# picr22-team-GibiBot-mainboard1.net
KiCad netlist of a schematic drawn in Altium Designer
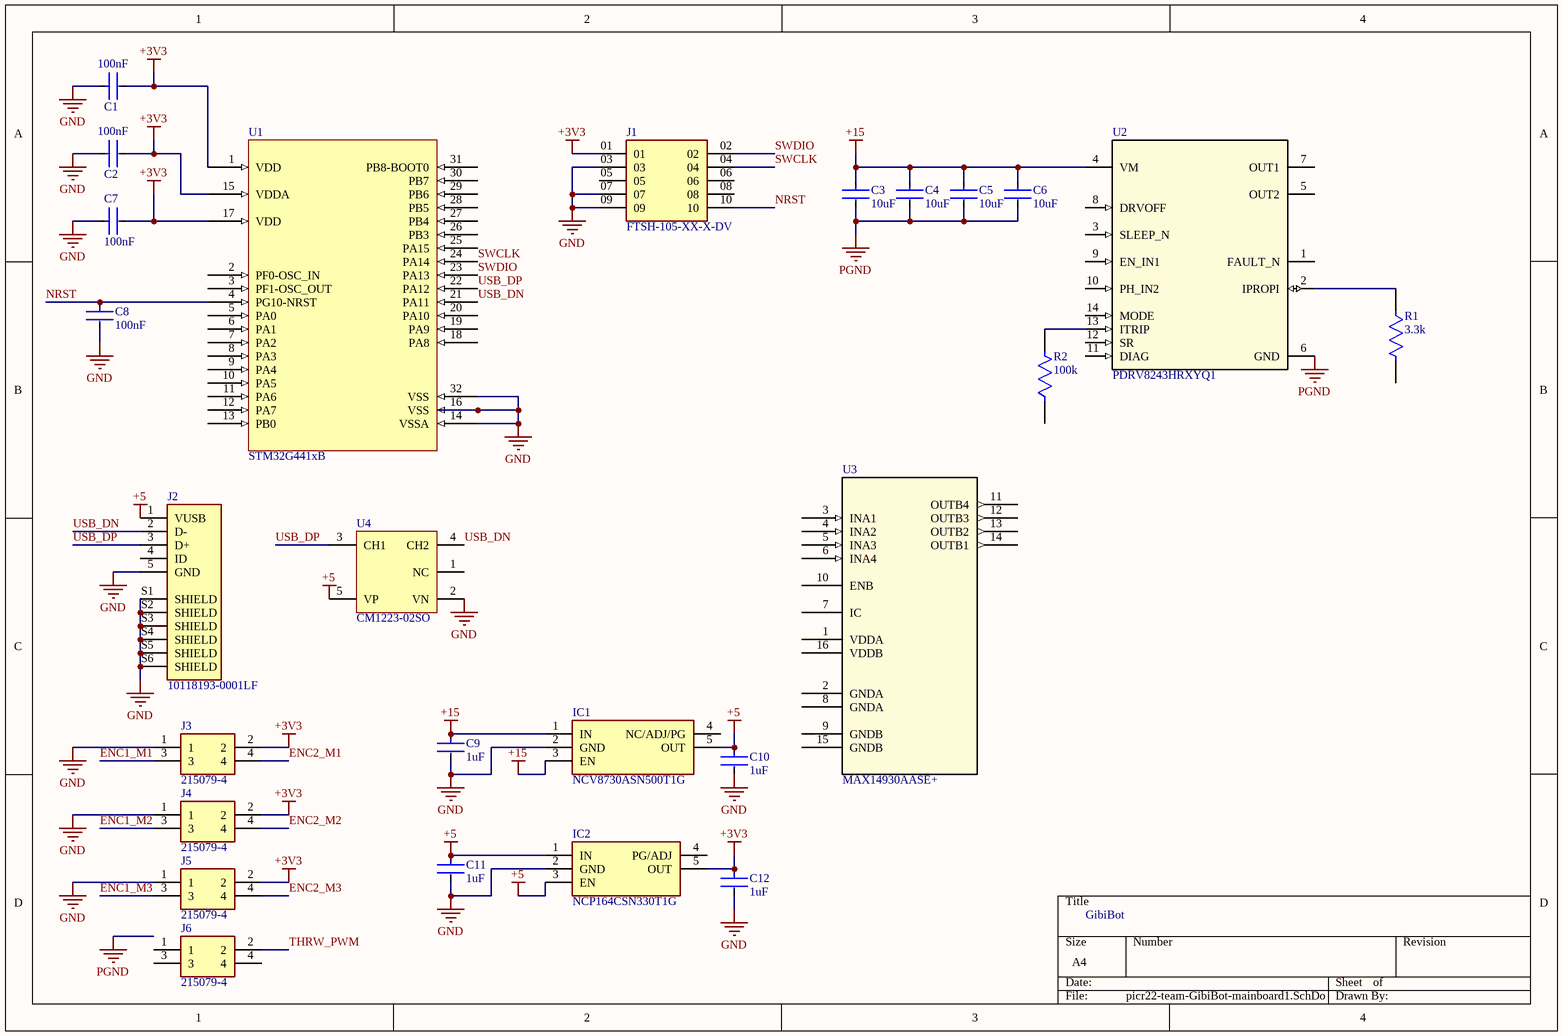
[diagram p0: picr22-team-GibiBot-mainboard1.SchDoc]

(export (version "E")
  (design (tool "Eeschema 10.0.6"))
  (components
    (comp (ref "C1")
      (value "CGA3E2X7R1H104K080AA")
      (footprint "FP-CGA3E-0_3-0_1-IPC_A")
      (description "Cap Ceramic 100nF 50V X7R 10% Pad SMD 0603 +125°C Automotive T/R")
      (fields
        (field (name "TOLERANCE") "10%")
        (field (name "CAPACITANCE") "100nF")
        (field (name "VOLTAGE") "50V")
      )
      (libsource (lib "Altium Content Vault") (part "b4654b650e69147ec39a6b967a45e02"))
    )
    (comp (ref "C2")
      (value "CGA3E2X7R1H104K080AA")
      (footprint "FP-CGA3E-0_3-0_1-IPC_A")
      (description "Cap Ceramic 100nF 50V X7R 10% Pad SMD 0603 +125°C Automotive T/R")
      (fields
        (field (name "TOLERANCE") "10%")
        (field (name "CAPACITANCE") "100nF")
        (field (name "VOLTAGE") "50V")
      )
      (libsource (lib "Altium Content Vault") (part "b4654b650e69147ec39a6b967a45e02"))
    )
    (comp (ref "C3")
      (value "CGA3E2X7R1H104K080AA")
      (footprint "FP-CGA3E-0_3-0_1-IPC_A")
      (description "Cap Ceramic 100nF 50V X7R 10% Pad SMD 0603 +125°C Automotive T/R")
      (fields
        (field (name "TOLERANCE") "10%")
        (field (name "CAPACITANCE") "10uF")
        (field (name "VOLTAGE") "50V")
      )
      (libsource (lib "Altium Content Vault") (part "b4654b650e69147ec39a6b967a45e02"))
    )
    (comp (ref "C4")
      (value "CGA3E2X7R1H104K080AA")
      (footprint "FP-CGA3E-0_3-0_1-IPC_A")
      (description "Cap Ceramic 100nF 50V X7R 10% Pad SMD 0603 +125°C Automotive T/R")
      (fields
        (field (name "TOLERANCE") "10%")
        (field (name "CAPACITANCE") "10uF")
        (field (name "VOLTAGE") "50V")
      )
      (libsource (lib "Altium Content Vault") (part "b4654b650e69147ec39a6b967a45e02"))
    )
    (comp (ref "C5")
      (value "CGA3E2X7R1H104K080AA")
      (footprint "FP-CGA3E-0_3-0_1-IPC_A")
      (description "Cap Ceramic 100nF 50V X7R 10% Pad SMD 0603 +125°C Automotive T/R")
      (fields
        (field (name "TOLERANCE") "10%")
        (field (name "CAPACITANCE") "10uF")
        (field (name "VOLTAGE") "50V")
      )
      (libsource (lib "Altium Content Vault") (part "b4654b650e69147ec39a6b967a45e02"))
    )
    (comp (ref "C6")
      (value "CGA3E2X7R1H104K080AA")
      (footprint "FP-CGA3E-0_3-0_1-IPC_A")
      (description "Cap Ceramic 100nF 50V X7R 10% Pad SMD 0603 +125°C Automotive T/R")
      (fields
        (field (name "TOLERANCE") "10%")
        (field (name "CAPACITANCE") "10uF")
        (field (name "VOLTAGE") "50V")
      )
      (libsource (lib "Altium Content Vault") (part "b4654b650e69147ec39a6b967a45e02"))
    )
    (comp (ref "C7")
      (value "CGA3E2X7R1H104K080AA")
      (footprint "FP-CGA3E-0_3-0_1-IPC_A")
      (description "Cap Ceramic 100nF 50V X7R 10% Pad SMD 0603 +125°C Automotive T/R")
      (fields
        (field (name "TOLERANCE") "10%")
        (field (name "CAPACITANCE") "100nF")
        (field (name "VOLTAGE") "50V")
      )
      (libsource (lib "Altium Content Vault") (part "b4654b650e69147ec39a6b967a45e02"))
    )
    (comp (ref "C8")
      (value "CGA3E2X7R1H104K080AA")
      (footprint "FP-CGA3E-0_3-0_1-IPC_A")
      (description "Cap Ceramic 100nF 50V X7R 10% Pad SMD 0603 +125°C Automotive T/R")
      (fields
        (field (name "TOLERANCE") "10%")
        (field (name "CAPACITANCE") "100nF")
        (field (name "VOLTAGE") "50V")
      )
      (libsource (lib "Altium Content Vault") (part "b4654b650e69147ec39a6b967a45e02"))
    )
    (comp (ref "C9")
      (value "CGA3E2X7R1H104K080AA")
      (footprint "FP-CGA3E-0_3-0_1-IPC_A")
      (description "Cap Ceramic 100nF 50V X7R 10% Pad SMD 0603 +125°C Automotive T/R")
      (fields
        (field (name "TOLERANCE") "10%")
        (field (name "CAPACITANCE") "1uF")
        (field (name "VOLTAGE") "50V")
      )
      (libsource (lib "Altium Content Vault") (part "b4654b650e69147ec39a6b967a45e02"))
    )
    (comp (ref "C10")
      (value "CGA3E2X7R1H104K080AA")
      (footprint "FP-CGA3E-0_3-0_1-IPC_A")
      (description "Cap Ceramic 100nF 50V X7R 10% Pad SMD 0603 +125°C Automotive T/R")
      (fields
        (field (name "TOLERANCE") "10%")
        (field (name "CAPACITANCE") "1uF")
        (field (name "VOLTAGE") "50V")
      )
      (libsource (lib "Altium Content Vault") (part "b4654b650e69147ec39a6b967a45e02"))
    )
    (comp (ref "C11")
      (value "CGA3E2X7R1H104K080AA")
      (footprint "FP-CGA3E-0_3-0_1-IPC_A")
      (description "Cap Ceramic 100nF 50V X7R 10% Pad SMD 0603 +125°C Automotive T/R")
      (fields
        (field (name "TOLERANCE") "10%")
        (field (name "CAPACITANCE") "1uF")
        (field (name "VOLTAGE") "50V")
      )
      (libsource (lib "Altium Content Vault") (part "b4654b650e69147ec39a6b967a45e02"))
    )
    (comp (ref "C12")
      (value "CGA3E2X7R1H104K080AA")
      (footprint "FP-CGA3E-0_3-0_1-IPC_A")
      (description "Cap Ceramic 100nF 50V X7R 10% Pad SMD 0603 +125°C Automotive T/R")
      (fields
        (field (name "TOLERANCE") "10%")
        (field (name "CAPACITANCE") "1uF")
        (field (name "VOLTAGE") "50V")
      )
      (libsource (lib "Altium Content Vault") (part "b4654b650e69147ec39a6b967a45e02"))
    )
    (comp (ref "IC1")
      (value "NCV8730ASN500T1G")
      (footprint "SamacSys:SOT95P275X110-5N")
      (description "Integrated Circuit")
      (fields (field (name "MOUSER PART NUMBER") "863-NCV8730ASN500T1G"))
      (libsource (lib "*") (part "NCV8730ASN500T1G"))
    )
    (comp (ref "IC2")
      (value "NCP164CSN330T1G")
      (footprint "SamacSys:SOT95P275X110-5N")
      (description "Integrated Circuit")
      (fields (field (name "MOUSER PART NUMBER") "863-NCP164CSN330T1G"))
      (libsource (lib "*") (part "NCP164CSN330T1G"))
    )
    (comp (ref "J1")
      (value "FTSH-105-XX-X-DV")
      (footprint "SAMTEC_FTSH-105-XX-X-DV")
      (description "Connector Header Surface Mount 10 position 0.050\" (1.27mm)")
      (libsource (lib "FTSH-105-XX-X-DV") (part "FTSH-105-XX-X-DV"))
    )
    (comp (ref "J2")
      (value "10118193-0001LF")
      (footprint "FCI_10118193-0001LF")
      (description "USB - micro B USB 2.0 Receptacle Connector 5 Position Surface Mount, Right Angle; Through Hole")
      (fields (field (name "MF") "Amphenol ICC"))
      (libsource (lib "10118193-0001LF") (part "10118193-0001LF"))
    )
    (comp (ref "J3")
      (value "215079-4")
      (footprint "TE_215079-4")
      (description "4 Position Receptacle Connector Through Hole")
      (fields (field (name "MF") "TE Connectivity"))
      (libsource (lib "215079-4") (part "215079-4"))
    )
    (comp (ref "J4")
      (value "215079-4")
      (footprint "TE_215079-4")
      (description "4 Position Receptacle Connector Through Hole")
      (fields (field (name "MF") "TE Connectivity"))
      (libsource (lib "215079-4") (part "215079-4"))
    )
    (comp (ref "J5")
      (value "215079-4")
      (footprint "TE_215079-4")
      (description "4 Position Receptacle Connector Through Hole")
      (fields (field (name "MF") "TE Connectivity"))
      (libsource (lib "215079-4") (part "215079-4"))
    )
    (comp (ref "J6")
      (value "215079-4")
      (footprint "TE_215079-4")
      (description "4 Position Receptacle Connector Through Hole")
      (fields (field (name "MF") "TE Connectivity"))
      (libsource (lib "215079-4") (part "215079-4"))
    )
    (comp (ref "R1")
      (value "CRCW040232K4FKED")
      (footprint "FP-CRCW0402-e3-MFG")
      (description "RES Thick Film, 32.4kΩ, 1%, 0.063W, 100ppm/°C, 0402")
      (fields (field (name "RESISTANCE") "3.3k") (field (name "TOLERANCE") "1%"))
      (libsource (lib "Altium Content Vault") (part "1029c3af85768c4190bb7ad29bc67b5"))
    )
    (comp (ref "R2")
      (value "CRCW040232K4FKED")
      (footprint "FP-CRCW0402-e3-MFG")
      (description "RES Thick Film, 32.4kΩ, 1%, 0.063W, 100ppm/°C, 0402")
      (fields (field (name "RESISTANCE") "100k") (field (name "TOLERANCE") "1%"))
      (libsource (lib "Altium Content Vault") (part "1029c3af85768c4190bb7ad29bc67b5"))
    )
    (comp (ref "U1")
      (value "STM32G441xB")
      (footprint "TQFP80P900X900X160-32N")
      (libsource (lib "picr22-team-GibiBot-mainboard") (part "STM32G441xB"))
    )
    (comp (ref "U2")
      (value "PDRV8243HRXYQ1")
      (footprint "RXY0014A-MFG")
      (description "No Description Available")
      (fields (field (name "COPYRIGHT") "Copyright (C) 2022 Ultra Librarian. All rights reserved."))
      (libsource (lib "PDRV8243HRXYQ1") (part "PDRV8243HRXYQ1"))
    )
    (comp (ref "U3")
      (value "MAX14930AASE+")
      (footprint "21-0041_S16+1_MXM")
      (description "No Description Available")
      (fields (field (name "COPYRIGHT") "Copyright (C) 2022 Ultra Librarian. All rights reserved."))
      (libsource (lib "MAX14930AASE&plus_") (part "MAX14930AASE+"))
    )
    (comp (ref "U4")
      (value "CM1223-02SO")
      (footprint "ONSC-SOT23-5-527AH-01_L")
      (fields (field (name "MANUFACTURER") "On Semiconductor"))
      (libsource (lib "Altium Content Vault") (part "ONSC-CM1223-SOT-23-5-527AH-01"))
    )
  )
  (nets
    (net (code "1") (name "+3V3") (class "Default")
      (node (ref "C1") (pin "2") (pinfunction "2_2") (pintype "passive"))
      (node (ref "C12") (pin "1") (pinfunction "1_1") (pintype "passive"))
      (node (ref "C2") (pin "2") (pinfunction "2_2") (pintype "passive"))
      (node (ref "C7") (pin "2") (pinfunction "2_2") (pintype "passive"))
      (node (ref "IC2") (pin "5") (pinfunction "OUT_5") (pintype "passive"))
      (node (ref "J1") (pin "01") (pinfunction "01_01") (pintype "passive"))
      (node (ref "J3") (pin "2") (pinfunction "2_2") (pintype "passive"))
      (node (ref "J4") (pin "2") (pinfunction "2_2") (pintype "passive"))
      (node (ref "J5") (pin "2") (pinfunction "2_2") (pintype "passive"))
      (node (ref "U1") (pin "1") (pinfunction "VDD_1") (pintype "input"))
      (node (ref "U1") (pin "15") (pinfunction "VDDA_15") (pintype "input"))
      (node (ref "U1") (pin "17") (pinfunction "VDD_17") (pintype "input"))
    )
    (net (code "2") (name "+5") (class "Default")
      (node (ref "C10") (pin "1") (pinfunction "1_1") (pintype "passive"))
      (node (ref "C11") (pin "1") (pinfunction "1_1") (pintype "passive"))
      (node (ref "IC1") (pin "5") (pinfunction "OUT_5") (pintype "passive"))
      (node (ref "IC2") (pin "1") (pinfunction "IN_1") (pintype "passive"))
      (node (ref "IC2") (pin "3") (pinfunction "EN_3") (pintype "passive"))
      (node (ref "J2") (pin "1") (pinfunction "VUSB_1") (pintype "passive"))
      (node (ref "U4") (pin "5") (pinfunction "VP_5") (pintype "power_in"))
    )
    (net (code "3") (name "+15") (class "Default")
      (node (ref "C3") (pin "1") (pinfunction "1_1") (pintype "passive"))
      (node (ref "C4") (pin "1") (pinfunction "1_1") (pintype "passive"))
      (node (ref "C5") (pin "1") (pinfunction "1_1") (pintype "passive"))
      (node (ref "C6") (pin "1") (pinfunction "1_1") (pintype "passive"))
      (node (ref "C9") (pin "1") (pinfunction "1_1") (pintype "passive"))
      (node (ref "IC1") (pin "1") (pinfunction "IN_1") (pintype "passive"))
      (node (ref "IC1") (pin "3") (pinfunction "EN_3") (pintype "passive"))
      (node (ref "U2") (pin "4") (pinfunction "VM_4") (pintype "power_in"))
    )
    (net (code "4") (name "/ENC1_M1") (class "Default")
      (node (ref "J3") (pin "3") (pinfunction "3_3") (pintype "passive"))
    )
    (net (code "5") (name "/ENC1_M2") (class "Default")
      (node (ref "J4") (pin "3") (pinfunction "3_3") (pintype "passive"))
    )
    (net (code "6") (name "/ENC1_M3") (class "Default")
      (node (ref "J5") (pin "3") (pinfunction "3_3") (pintype "passive"))
    )
    (net (code "7") (name "/ENC2_M1") (class "Default")
      (node (ref "J3") (pin "4") (pinfunction "4_4") (pintype "passive"))
    )
    (net (code "8") (name "/ENC2_M2") (class "Default")
      (node (ref "J4") (pin "4") (pinfunction "4_4") (pintype "passive"))
    )
    (net (code "9") (name "/ENC2_M3") (class "Default")
      (node (ref "J5") (pin "4") (pinfunction "4_4") (pintype "passive"))
    )
    (net (code "10") (name "/NRST") (class "Default")
      (node (ref "C8") (pin "1") (pinfunction "1_1") (pintype "passive"))
      (node (ref "J1") (pin "10") (pinfunction "10_10") (pintype "passive"))
      (node (ref "U1") (pin "4") (pinfunction "PG10-NRST_4") (pintype "input"))
    )
    (net (code "11") (name "/SWCLK") (class "Default")
      (node (ref "J1") (pin "04") (pinfunction "04_04") (pintype "passive"))
      (node (ref "U1") (pin "24") (pinfunction "PA14_24") (pintype "input"))
    )
    (net (code "12") (name "/SWDIO") (class "Default")
      (node (ref "J1") (pin "02") (pinfunction "02_02") (pintype "passive"))
      (node (ref "U1") (pin "23") (pinfunction "PA13_23") (pintype "input"))
    )
    (net (code "13") (name "/THRW_PWM") (class "Default")
      (node (ref "J6") (pin "2") (pinfunction "2_2") (pintype "passive"))
    )
    (net (code "14") (name "/USB_DN") (class "Default")
      (node (ref "J2") (pin "2") (pinfunction "D-_2") (pintype "passive"))
      (node (ref "U1") (pin "21") (pinfunction "PA11_21") (pintype "input"))
      (node (ref "U4") (pin "4") (pinfunction "CH2_4") (pintype "passive"))
    )
    (net (code "15") (name "/USB_DP") (class "Default")
      (node (ref "J2") (pin "3") (pinfunction "D+_3") (pintype "passive"))
      (node (ref "U1") (pin "22") (pinfunction "PA12_22") (pintype "input"))
      (node (ref "U4") (pin "3") (pinfunction "CH1_3") (pintype "passive"))
    )
    (net (code "16") (name "GND") (class "Default")
      (node (ref "C1") (pin "1") (pinfunction "1_1") (pintype "passive"))
      (node (ref "C10") (pin "2") (pinfunction "2_2") (pintype "passive"))
      (node (ref "C11") (pin "2") (pinfunction "2_2") (pintype "passive"))
      (node (ref "C12") (pin "2") (pinfunction "2_2") (pintype "passive"))
      (node (ref "C2") (pin "1") (pinfunction "1_1") (pintype "passive"))
      (node (ref "C7") (pin "1") (pinfunction "1_1") (pintype "passive"))
      (node (ref "C8") (pin "2") (pinfunction "2_2") (pintype "passive"))
      (node (ref "C9") (pin "2") (pinfunction "2_2") (pintype "passive"))
      (node (ref "IC1") (pin "2") (pinfunction "GND_2") (pintype "passive"))
      (node (ref "IC2") (pin "2") (pinfunction "GND_2") (pintype "passive"))
      (node (ref "J1") (pin "03") (pinfunction "03_03") (pintype "passive"))
      (node (ref "J1") (pin "07") (pinfunction "07_07") (pintype "passive"))
      (node (ref "J1") (pin "09") (pinfunction "09_09") (pintype "passive"))
      (node (ref "J2") (pin "5") (pinfunction "GND_5") (pintype "passive"))
      (node (ref "J2") (pin "S1") (pinfunction "SHIELD_S1") (pintype "passive"))
      (node (ref "J2") (pin "S2") (pinfunction "SHIELD_S2") (pintype "passive"))
      (node (ref "J2") (pin "S3") (pinfunction "SHIELD_S3") (pintype "passive"))
      (node (ref "J2") (pin "S4") (pinfunction "SHIELD_S4") (pintype "passive"))
      (node (ref "J2") (pin "S5") (pinfunction "SHIELD_S5") (pintype "passive"))
      (node (ref "J2") (pin "S6") (pinfunction "SHIELD_S6") (pintype "passive"))
      (node (ref "J3") (pin "1") (pinfunction "1_1") (pintype "passive"))
      (node (ref "J4") (pin "1") (pinfunction "1_1") (pintype "passive"))
      (node (ref "J5") (pin "1") (pinfunction "1_1") (pintype "passive"))
      (node (ref "U1") (pin "14") (pinfunction "VSSA_14") (pintype "input"))
      (node (ref "U1") (pin "16") (pinfunction "VSS_16") (pintype "input"))
      (node (ref "U1") (pin "32") (pinfunction "VSS_32") (pintype "input"))
      (node (ref "U4") (pin "2") (pinfunction "VN_2") (pintype "power_in"))
    )
    (net (code "17") (name "Net-(U2-IPROPI)") (class "Default")
      (node (ref "R1") (pin "1") (pinfunction "1_1") (pintype "passive"))
      (node (ref "U2") (pin "2") (pinfunction "IPROPI_2") (pintype "bidirectional"))
    )
    (net (code "18") (name "Net-(U2-ITRIP)") (class "Default")
      (node (ref "R2") (pin "2") (pinfunction "2_2") (pintype "passive"))
      (node (ref "U2") (pin "13") (pinfunction "ITRIP_13") (pintype "input"))
    )
    (net (code "19") (name "PGND") (class "Default")
      (node (ref "C3") (pin "2") (pinfunction "2_2") (pintype "passive"))
      (node (ref "C4") (pin "2") (pinfunction "2_2") (pintype "passive"))
      (node (ref "C5") (pin "2") (pinfunction "2_2") (pintype "passive"))
      (node (ref "C6") (pin "2") (pinfunction "2_2") (pintype "passive"))
      (node (ref "U2") (pin "6") (pinfunction "GND_6") (pintype "power_in"))
    )
    (net (code "20") (name "unconnected-(IC1-NC{slash}ADJ{slash}PG-Pad4)") (class "Default")
      (node (ref "IC1") (pin "4") (pinfunction "NC/ADJ/PG_4") (pintype "passive"))
    )
    (net (code "21") (name "unconnected-(IC2-PG{slash}ADJ-Pad4)") (class "Default")
      (node (ref "IC2") (pin "4") (pinfunction "PG/ADJ_4") (pintype "passive"))
    )
    (net (code "22") (name "unconnected-(J1-Pad05)") (class "Default")
      (node (ref "J1") (pin "05") (pinfunction "05_05") (pintype "passive"))
    )
    (net (code "23") (name "unconnected-(J1-Pad06)") (class "Default")
      (node (ref "J1") (pin "06") (pinfunction "06_06") (pintype "passive"))
    )
    (net (code "24") (name "unconnected-(J1-Pad08)") (class "Default")
      (node (ref "J1") (pin "08") (pinfunction "08_08") (pintype "passive"))
    )
    (net (code "25") (name "unconnected-(J2-ID-Pad4)") (class "Default")
      (node (ref "J2") (pin "4") (pinfunction "ID_4") (pintype "passive"))
    )
    (net (code "26") (name "unconnected-(J6-Pad1)") (class "Default")
      (node (ref "J6") (pin "1") (pinfunction "1_1") (pintype "passive"))
    )
    (net (code "27") (name "unconnected-(J6-Pad3)") (class "Default")
      (node (ref "J6") (pin "3") (pinfunction "3_3") (pintype "passive"))
    )
    (net (code "28") (name "unconnected-(J6-Pad4)") (class "Default")
      (node (ref "J6") (pin "4") (pinfunction "4_4") (pintype "passive"))
    )
    (net (code "29") (name "unconnected-(R1-Pad2)") (class "Default")
      (node (ref "R1") (pin "2") (pinfunction "2_2") (pintype "passive"))
    )
    (net (code "30") (name "unconnected-(R2-Pad1)") (class "Default")
      (node (ref "R2") (pin "1") (pinfunction "1_1") (pintype "passive"))
    )
    (net (code "31") (name "unconnected-(U1-PA0-Pad5)") (class "Default")
      (node (ref "U1") (pin "5") (pinfunction "PA0_5") (pintype "input"))
    )
    (net (code "32") (name "unconnected-(U1-PA1-Pad6)") (class "Default")
      (node (ref "U1") (pin "6") (pinfunction "PA1_6") (pintype "input"))
    )
    (net (code "33") (name "unconnected-(U1-PA2-Pad7)") (class "Default")
      (node (ref "U1") (pin "7") (pinfunction "PA2_7") (pintype "input"))
    )
    (net (code "34") (name "unconnected-(U1-PA3-Pad8)") (class "Default")
      (node (ref "U1") (pin "8") (pinfunction "PA3_8") (pintype "input"))
    )
    (net (code "35") (name "unconnected-(U1-PA4-Pad9)") (class "Default")
      (node (ref "U1") (pin "9") (pinfunction "PA4_9") (pintype "input"))
    )
    (net (code "36") (name "unconnected-(U1-PA5-Pad10)") (class "Default")
      (node (ref "U1") (pin "10") (pinfunction "PA5_10") (pintype "input"))
    )
    (net (code "37") (name "unconnected-(U1-PA6-Pad11)") (class "Default")
      (node (ref "U1") (pin "11") (pinfunction "PA6_11") (pintype "input"))
    )
    (net (code "38") (name "unconnected-(U1-PA7-Pad12)") (class "Default")
      (node (ref "U1") (pin "12") (pinfunction "PA7_12") (pintype "input"))
    )
    (net (code "39") (name "unconnected-(U1-PA8-Pad18)") (class "Default")
      (node (ref "U1") (pin "18") (pinfunction "PA8_18") (pintype "input"))
    )
    (net (code "40") (name "unconnected-(U1-PA9-Pad19)") (class "Default")
      (node (ref "U1") (pin "19") (pinfunction "PA9_19") (pintype "input"))
    )
    (net (code "41") (name "unconnected-(U1-PA10-Pad20)") (class "Default")
      (node (ref "U1") (pin "20") (pinfunction "PA10_20") (pintype "input"))
    )
    (net (code "42") (name "unconnected-(U1-PA15-Pad25)") (class "Default")
      (node (ref "U1") (pin "25") (pinfunction "PA15_25") (pintype "input"))
    )
    (net (code "43") (name "unconnected-(U1-PB0-Pad13)") (class "Default")
      (node (ref "U1") (pin "13") (pinfunction "PB0_13") (pintype "input"))
    )
    (net (code "44") (name "unconnected-(U1-PB3-Pad26)") (class "Default")
      (node (ref "U1") (pin "26") (pinfunction "PB3_26") (pintype "input"))
    )
    (net (code "45") (name "unconnected-(U1-PB4-Pad27)") (class "Default")
      (node (ref "U1") (pin "27") (pinfunction "PB4_27") (pintype "input"))
    )
    (net (code "46") (name "unconnected-(U1-PB5-Pad28)") (class "Default")
      (node (ref "U1") (pin "28") (pinfunction "PB5_28") (pintype "input"))
    )
    (net (code "47") (name "unconnected-(U1-PB6-Pad29)") (class "Default")
      (node (ref "U1") (pin "29") (pinfunction "PB6_29") (pintype "input"))
    )
    (net (code "48") (name "unconnected-(U1-PB7-Pad30)") (class "Default")
      (node (ref "U1") (pin "30") (pinfunction "PB7_30") (pintype "input"))
    )
    (net (code "49") (name "unconnected-(U1-PB8-BOOT0-Pad31)") (class "Default")
      (node (ref "U1") (pin "31") (pinfunction "PB8-BOOT0_31") (pintype "input"))
    )
    (net (code "50") (name "unconnected-(U1-PF0-OSC_IN-Pad2)") (class "Default")
      (node (ref "U1") (pin "2") (pinfunction "PF0-OSC_IN_2") (pintype "input"))
    )
    (net (code "51") (name "unconnected-(U1-PF1-OSC_OUT-Pad3)") (class "Default")
      (node (ref "U1") (pin "3") (pinfunction "PF1-OSC_OUT_3") (pintype "input"))
    )
    (net (code "52") (name "unconnected-(U2-DIAG-Pad11)") (class "Default")
      (node (ref "U2") (pin "11") (pinfunction "DIAG_11") (pintype "input"))
    )
    (net (code "53") (name "unconnected-(U2-DRVOFF-Pad8)") (class "Default")
      (node (ref "U2") (pin "8") (pinfunction "DRVOFF_8") (pintype "input"))
    )
    (net (code "54") (name "unconnected-(U2-EN_IN1-Pad9)") (class "Default")
      (node (ref "U2") (pin "9") (pinfunction "EN_IN1_9") (pintype "input"))
    )
    (net (code "55") (name "unconnected-(U2-FAULT_N-Pad1)") (class "Default")
      (node (ref "U2") (pin "1") (pinfunction "FAULT_N_1") (pintype "open_collector"))
    )
    (net (code "56") (name "unconnected-(U2-MODE-Pad14)") (class "Default")
      (node (ref "U2") (pin "14") (pinfunction "MODE_14") (pintype "input"))
    )
    (net (code "57") (name "unconnected-(U2-OUT1-Pad7)") (class "Default")
      (node (ref "U2") (pin "7") (pinfunction "OUT1_7") (pintype "passive"))
    )
    (net (code "58") (name "unconnected-(U2-OUT2-Pad5)") (class "Default")
      (node (ref "U2") (pin "5") (pinfunction "OUT2_5") (pintype "passive"))
    )
    (net (code "59") (name "unconnected-(U2-PH_IN2-Pad10)") (class "Default")
      (node (ref "U2") (pin "10") (pinfunction "PH_IN2_10") (pintype "input"))
    )
    (net (code "60") (name "unconnected-(U2-SLEEP_N-Pad3)") (class "Default")
      (node (ref "U2") (pin "3") (pinfunction "SLEEP_N_3") (pintype "input"))
    )
    (net (code "61") (name "unconnected-(U2-SR-Pad12)") (class "Default")
      (node (ref "U2") (pin "12") (pinfunction "SR_12") (pintype "input"))
    )
    (net (code "62") (name "unconnected-(U3-ENB-Pad10)") (class "Default")
      (node (ref "U3") (pin "10") (pinfunction "ENB_10") (pintype "passive"))
    )
    (net (code "63") (name "unconnected-(U3-GNDA-Pad2)") (class "Default")
      (node (ref "U3") (pin "2") (pinfunction "GNDA_2") (pintype "power_in"))
    )
    (net (code "64") (name "unconnected-(U3-GNDA-Pad8)") (class "Default")
      (node (ref "U3") (pin "8") (pinfunction "GNDA_8") (pintype "power_in"))
    )
    (net (code "65") (name "unconnected-(U3-GNDB-Pad9)") (class "Default")
      (node (ref "U3") (pin "9") (pinfunction "GNDB_9") (pintype "power_in"))
    )
    (net (code "66") (name "unconnected-(U3-GNDB-Pad15)") (class "Default")
      (node (ref "U3") (pin "15") (pinfunction "GNDB_15") (pintype "power_in"))
    )
    (net (code "67") (name "unconnected-(U3-IC-Pad7)") (class "Default")
      (node (ref "U3") (pin "7") (pinfunction "IC_7") (pintype "passive"))
    )
    (net (code "68") (name "unconnected-(U3-INA1-Pad3)") (class "Default")
      (node (ref "U3") (pin "3") (pinfunction "INA1_3") (pintype "input"))
    )
    (net (code "69") (name "unconnected-(U3-INA2-Pad4)") (class "Default")
      (node (ref "U3") (pin "4") (pinfunction "INA2_4") (pintype "input"))
    )
    (net (code "70") (name "unconnected-(U3-INA3-Pad5)") (class "Default")
      (node (ref "U3") (pin "5") (pinfunction "INA3_5") (pintype "input"))
    )
    (net (code "71") (name "unconnected-(U3-INA4-Pad6)") (class "Default")
      (node (ref "U3") (pin "6") (pinfunction "INA4_6") (pintype "input"))
    )
    (net (code "72") (name "unconnected-(U3-OUTB1-Pad14)") (class "Default")
      (node (ref "U3") (pin "14") (pinfunction "OUTB1_14") (pintype "output"))
    )
    (net (code "73") (name "unconnected-(U3-OUTB2-Pad13)") (class "Default")
      (node (ref "U3") (pin "13") (pinfunction "OUTB2_13") (pintype "output"))
    )
    (net (code "74") (name "unconnected-(U3-OUTB3-Pad12)") (class "Default")
      (node (ref "U3") (pin "12") (pinfunction "OUTB3_12") (pintype "output"))
    )
    (net (code "75") (name "unconnected-(U3-OUTB4-Pad11)") (class "Default")
      (node (ref "U3") (pin "11") (pinfunction "OUTB4_11") (pintype "output"))
    )
    (net (code "76") (name "unconnected-(U3-VDDA-Pad1)") (class "Default")
      (node (ref "U3") (pin "1") (pinfunction "VDDA_1") (pintype "power_in"))
    )
    (net (code "77") (name "unconnected-(U3-VDDB-Pad16)") (class "Default")
      (node (ref "U3") (pin "16") (pinfunction "VDDB_16") (pintype "power_in"))
    )
    (net (code "78") (name "unconnected-(U4-NC-Pad1)") (class "Default")
      (node (ref "U4") (pin "1") (pinfunction "NC_1") (pintype "passive"))
    )
  )
)
